# buckboost.net
KiCad netlist of a schematic drawn in Altium Designer
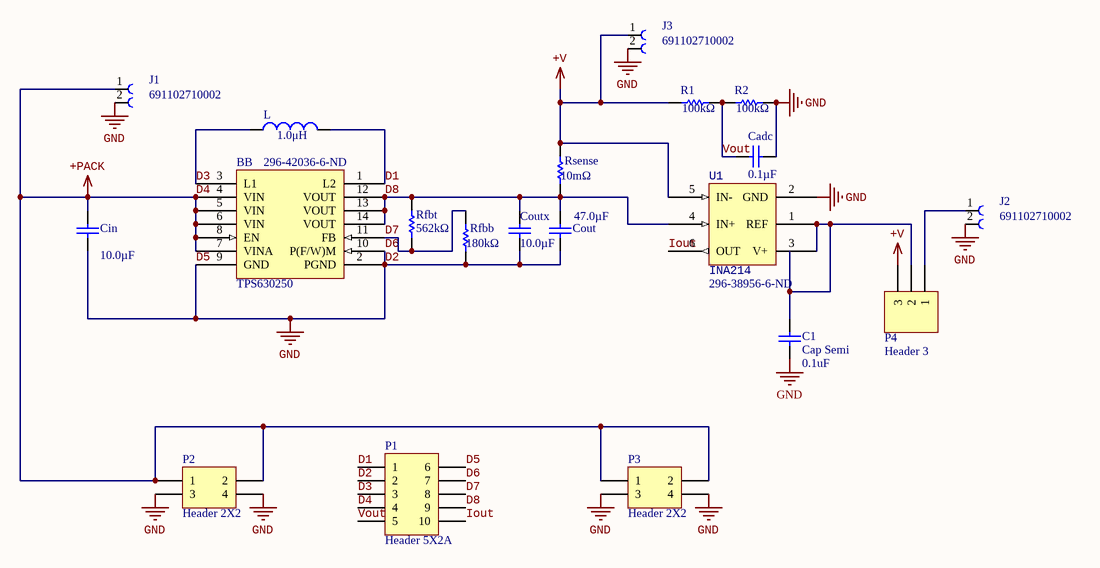
[diagram p0: buckboost.SchDoc]

(export (version "E")
  (design (tool "Eeschema 10.0.6"))
  (components
    (comp (ref "BB")
      (value "TPS630250")
      (footprint "EPS:RNC0014A")
      (description "Buck-boost converter")
      (fields (field (name "SUPPLIER PART NUMBER 1") "296-42036-6-ND"))
      (libsource (lib "heron-general") (part "TPS630250"))
    )
    (comp (ref "C1")
      (value "Cap Semi")
      (footprint "0603")
      (description "Capacitor (Semiconductor SIM Model)")
      (fields (field (name "ALTIUM_VALUE") "0.1uF") (field (name "PUBLISHER") "Altium Limited"))
      (libsource (lib "Miscellaneous Devices") (part "Cap Semi"))
    )
    (comp (ref "Cadc")
      (value "0.1µF")
      (footprint "0603")
      (description "Capacitor")
      (fields (field (name "Comment") "Cap") (field (name "PUBLISHER") "Altium Limited"))
      (libsource (lib "Miscellaneous Devices") (part "Cap"))
    )
    (comp (ref "Cin")
      (value "10.0µF")
      (footprint "0603")
      (description "Capacitor")
      (fields (field (name "Comment") "Cap") (field (name "PUBLISHER") "Altium Limited"))
      (libsource (lib "Miscellaneous Devices") (part "Cap"))
    )
    (comp (ref "Cout")
      (value "47.0µF")
      (footprint "1206")
      (description "Capacitor")
      (fields (field (name "Comment") "Cap") (field (name "PUBLISHER") "Altium Limited"))
      (libsource (lib "Miscellaneous Devices") (part "Cap"))
    )
    (comp (ref "Coutx")
      (value "10.0µF")
      (footprint "0603")
      (description "Capacitor")
      (fields (field (name "Comment") "Cap") (field (name "PUBLISHER") "Altium Limited"))
      (libsource (lib "Miscellaneous Devices") (part "Cap"))
    )
    (comp (ref "J1")
      (value "691102710002")
      (footprint "691102710002:691102710002")
      (description "102 Series 5mm Pitch Straight, PCB Terminal Block, Through Hole, 2 Way")
      (fields (field (name "MF") "Wurth Electronics"))
      (libsource (lib "691102710002") (part "691102710002"))
    )
    (comp (ref "J2")
      (value "691102710002")
      (footprint "691102710002:691102710002")
      (description "102 Series 5mm Pitch Straight, PCB Terminal Block, Through Hole, 2 Way")
      (fields (field (name "MF") "Wurth Electronics"))
      (libsource (lib "691102710002") (part "691102710002"))
    )
    (comp (ref "J3")
      (value "691102710002")
      (footprint "691102710002:691102710002")
      (description "102 Series 5mm Pitch Straight, PCB Terminal Block, Through Hole, 2 Way")
      (fields (field (name "MF") "Wurth Electronics"))
      (libsource (lib "691102710002") (part "691102710002"))
    )
    (comp (ref "L")
      (value "1.0μH")
      (footprint "IHLP-1212BZ")
      (description "Inductor")
      (fields (field (name "PUBLISHER") "Altium Limited"))
      (libsource (lib "Miscellaneous Devices") (part "Inductor"))
    )
    (comp (ref "P1")
      (value "Header 5X2A")
      (footprint "HDR2X5_CEN")
      (description "Header, 5-Pin, Dual row")
      (fields (field (name "PUBLISHER") "Altium Limited"))
      (libsource (lib "Miscellaneous Connectors") (part "Header 5X2A"))
    )
    (comp (ref "P2")
      (value "Header 2X2")
      (footprint "HDR2X2")
      (description "Header, 2-Pin, Dual row")
      (fields (field (name "PUBLISHER") "Altium Limited"))
      (libsource (lib "Miscellaneous Connectors") (part "Header 2X2"))
    )
    (comp (ref "P3")
      (value "Header 2X2")
      (footprint "HDR2X2")
      (description "Header, 2-Pin, Dual row")
      (fields (field (name "PUBLISHER") "Altium Limited"))
      (libsource (lib "Miscellaneous Connectors") (part "Header 2X2"))
    )
    (comp (ref "P4")
      (value "Header 3")
      (footprint "HDR1X3")
      (description "Header, 3-Pin")
      (fields (field (name "PUBLISHER") "Altium Limited"))
      (libsource (lib "Miscellaneous Connectors") (part "Header 3"))
    )
    (comp (ref "R1")
      (value "100kΩ")
      (footprint "0603")
      (description "Resistor")
      (fields (field (name "Comment") "Res1") (field (name "PUBLISHER") "Altium Limited"))
      (libsource (lib "Miscellaneous Devices") (part "Res1"))
    )
    (comp (ref "R2")
      (value "100kΩ")
      (footprint "0603")
      (description "Resistor")
      (fields (field (name "Comment") "Res1") (field (name "PUBLISHER") "Altium Limited"))
      (libsource (lib "Miscellaneous Devices") (part "Res1"))
    )
    (comp (ref "Rfbb")
      (value "180kΩ")
      (footprint "0603")
      (description "Resistor")
      (fields (field (name "Comment") "Res1") (field (name "PUBLISHER") "Altium Limited"))
      (libsource (lib "Miscellaneous Devices") (part "Res1"))
    )
    (comp (ref "Rfbt")
      (value "562kΩ")
      (footprint "0603")
      (description "Resistor")
      (fields (field (name "Comment") "Rfbt") (field (name "PUBLISHER") "Altium Limited"))
      (libsource (lib "Miscellaneous Devices") (part "Res1"))
    )
    (comp (ref "Rsense")
      (value "10mΩ")
      (footprint "0603")
      (description "Resistor")
      (fields (field (name "Comment") "Rsense") (field (name "PUBLISHER") "Altium Limited"))
      (libsource (lib "Miscellaneous Devices") (part "Res1"))
    )
    (comp (ref "U1")
      (value "INA214")
      (footprint "EPS:SOT65P210X110-6N")
      (description "Current monitor")
      (fields (field (name "SUPPLIER PART NUMBER 1") "296-38956-6-ND"))
      (libsource (lib "heron-general") (part "INA214"))
    )
  )
  (nets
    (net (code "1") (name "+PACK") (class "Default")
      (node (ref "BB") (pin "4") (pinfunction "VIN_4") (pintype "power_in"))
      (node (ref "BB") (pin "5") (pinfunction "VIN_5") (pintype "power_in"))
      (node (ref "BB") (pin "6") (pinfunction "VIN_6") (pintype "power_in"))
      (node (ref "BB") (pin "7") (pinfunction "VINA_7") (pintype "power_in"))
      (node (ref "BB") (pin "8") (pinfunction "EN_8") (pintype "input"))
      (node (ref "Cin") (pin "2") (pinfunction "2_2") (pintype "passive"))
      (node (ref "J1") (pin "1") (pinfunction "1_1") (pintype "passive"))
      (node (ref "P1") (pin "4") (pinfunction "4_4") (pintype "passive"))
      (node (ref "P2") (pin "1") (pinfunction "1_1") (pintype "passive"))
      (node (ref "P2") (pin "2") (pinfunction "2_2") (pintype "passive"))
      (node (ref "P3") (pin "1") (pinfunction "1_1") (pintype "passive"))
      (node (ref "P3") (pin "2") (pinfunction "2_2") (pintype "passive"))
    )
    (net (code "2") (name "+V") (class "Default")
      (node (ref "J3") (pin "1") (pinfunction "1_1") (pintype "passive"))
      (node (ref "P4") (pin "3") (pinfunction "3_3") (pintype "passive"))
      (node (ref "R1") (pin "1") (pinfunction "1_1") (pintype "passive"))
      (node (ref "Rsense") (pin "2") (pinfunction "2_2") (pintype "passive"))
      (node (ref "U1") (pin "5") (pinfunction "IN-_5") (pintype "input"))
    )
    (net (code "3") (name "/D1") (class "Default")
      (node (ref "BB") (pin "1") (pinfunction "L2_1") (pintype "power_in"))
      (node (ref "L") (pin "2") (pinfunction "2_2") (pintype "passive"))
      (node (ref "P1") (pin "1") (pinfunction "1_1") (pintype "passive"))
    )
    (net (code "4") (name "/D3") (class "Default")
      (node (ref "BB") (pin "3") (pinfunction "L1_3") (pintype "power_in"))
      (node (ref "L") (pin "1") (pinfunction "1_1") (pintype "passive"))
      (node (ref "P1") (pin "3") (pinfunction "3_3") (pintype "passive"))
    )
    (net (code "5") (name "/D7") (class "Default")
      (node (ref "BB") (pin "11") (pinfunction "FB_11") (pintype "input"))
      (node (ref "P1") (pin "8") (pinfunction "8_8") (pintype "passive"))
      (node (ref "Rfbb") (pin "2") (pinfunction "2_2") (pintype "passive"))
      (node (ref "Rfbt") (pin "2") (pinfunction "2_2") (pintype "passive"))
    )
    (net (code "6") (name "/D8") (class "Default")
      (node (ref "BB") (pin "12") (pinfunction "VOUT_12") (pintype "passive"))
      (node (ref "BB") (pin "13") (pinfunction "VOUT_13") (pintype "passive"))
      (node (ref "BB") (pin "14") (pinfunction "VOUT_14") (pintype "passive"))
      (node (ref "Cout") (pin "2") (pinfunction "2_2") (pintype "passive"))
      (node (ref "Coutx") (pin "2") (pinfunction "2_2") (pintype "passive"))
      (node (ref "P1") (pin "9") (pinfunction "9_9") (pintype "passive"))
      (node (ref "Rfbt") (pin "1") (pinfunction "1_1") (pintype "passive"))
      (node (ref "Rsense") (pin "1") (pinfunction "1_1") (pintype "passive"))
      (node (ref "U1") (pin "4") (pinfunction "IN+_4") (pintype "input"))
    )
    (net (code "7") (name "/Iout") (class "Default")
      (node (ref "P1") (pin "10") (pinfunction "10_10") (pintype "passive"))
      (node (ref "U1") (pin "6") (pinfunction "OUT_6") (pintype "output"))
    )
    (net (code "8") (name "/Vout") (class "Default")
      (node (ref "Cadc") (pin "2") (pinfunction "2_2") (pintype "passive"))
      (node (ref "P1") (pin "5") (pinfunction "5_5") (pintype "passive"))
      (node (ref "R1") (pin "2") (pinfunction "2_2") (pintype "passive"))
      (node (ref "R2") (pin "1") (pinfunction "1_1") (pintype "passive"))
    )
    (net (code "9") (name "GND") (class "Default")
      (node (ref "BB") (pin "10") (pinfunction "P(F/W)M_10") (pintype "input"))
      (node (ref "BB") (pin "2") (pinfunction "PGND_2") (pintype "power_in"))
      (node (ref "BB") (pin "9") (pinfunction "GND_9") (pintype "power_in"))
      (node (ref "C1") (pin "1") (pinfunction "1_1") (pintype "passive"))
      (node (ref "Cadc") (pin "1") (pinfunction "1_1") (pintype "passive"))
      (node (ref "Cin") (pin "1") (pinfunction "1_1") (pintype "passive"))
      (node (ref "Cout") (pin "1") (pinfunction "1_1") (pintype "passive"))
      (node (ref "Coutx") (pin "1") (pinfunction "1_1") (pintype "passive"))
      (node (ref "J1") (pin "2") (pinfunction "2_2") (pintype "passive"))
      (node (ref "J2") (pin "2") (pinfunction "2_2") (pintype "passive"))
      (node (ref "J3") (pin "2") (pinfunction "2_2") (pintype "passive"))
      (node (ref "P1") (pin "2") (pinfunction "2_2") (pintype "passive"))
      (node (ref "P1") (pin "6") (pinfunction "6_6") (pintype "passive"))
      (node (ref "P1") (pin "7") (pinfunction "7_7") (pintype "passive"))
      (node (ref "P2") (pin "3") (pinfunction "3_3") (pintype "passive"))
      (node (ref "P2") (pin "4") (pinfunction "4_4") (pintype "passive"))
      (node (ref "P3") (pin "3") (pinfunction "3_3") (pintype "passive"))
      (node (ref "P3") (pin "4") (pinfunction "4_4") (pintype "passive"))
      (node (ref "R2") (pin "2") (pinfunction "2_2") (pintype "passive"))
      (node (ref "Rfbb") (pin "1") (pinfunction "1_1") (pintype "passive"))
      (node (ref "U1") (pin "2") (pinfunction "GND_2") (pintype "power_in"))
    )
    (net (code "10") (name "Net-(J2-Pad1)") (class "Default")
      (node (ref "J2") (pin "1") (pinfunction "1_1") (pintype "passive"))
      (node (ref "P4") (pin "1") (pinfunction "1_1") (pintype "passive"))
    )
    (net (code "11") (name "Net-(U1-REF)") (class "Default")
      (node (ref "C1") (pin "2") (pinfunction "2_2") (pintype "passive"))
      (node (ref "P4") (pin "2") (pinfunction "2_2") (pintype "passive"))
      (node (ref "U1") (pin "1") (pinfunction "REF_1") (pintype "passive"))
      (node (ref "U1") (pin "3") (pinfunction "V+_3") (pintype "power_in"))
    )
  )
)
